# ledarray.net
KiCad netlist of a schematic drawn in EAGLE
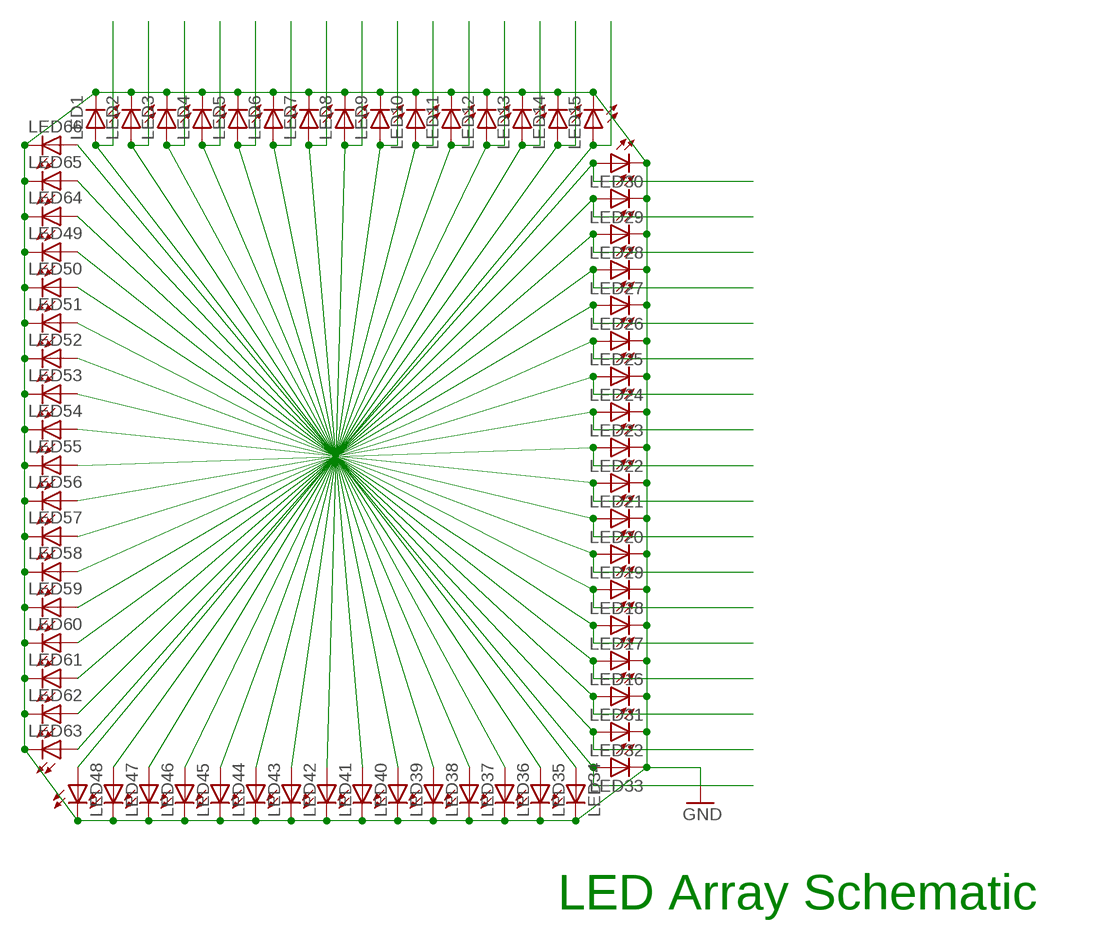
[diagram p0: schematic, sheet 1]

(export (version "E")
  (design (tool "Eeschema 10.0.6"))
  (components
    (comp (ref "LED1")
      (value "LED3MM")
      (footprint "eagle-import:LED3MM")
      (libsource (lib "eagle-import") (part "LED3MM"))
    )
    (comp (ref "LED2")
      (value "LED3MM")
      (footprint "eagle-import:LED3MM")
      (libsource (lib "eagle-import") (part "LED3MM"))
    )
    (comp (ref "LED3")
      (value "LED3MM")
      (footprint "eagle-import:LED3MM")
      (libsource (lib "eagle-import") (part "LED3MM"))
    )
    (comp (ref "LED4")
      (value "LED3MM")
      (footprint "eagle-import:LED3MM")
      (libsource (lib "eagle-import") (part "LED3MM"))
    )
    (comp (ref "LED5")
      (value "LED3MM")
      (footprint "eagle-import:LED3MM")
      (libsource (lib "eagle-import") (part "LED3MM"))
    )
    (comp (ref "LED6")
      (value "LED3MM")
      (footprint "eagle-import:LED3MM")
      (libsource (lib "eagle-import") (part "LED3MM"))
    )
    (comp (ref "LED7")
      (value "LED3MM")
      (footprint "eagle-import:LED3MM")
      (libsource (lib "eagle-import") (part "LED3MM"))
    )
    (comp (ref "LED8")
      (value "LED3MM")
      (footprint "eagle-import:LED3MM")
      (libsource (lib "eagle-import") (part "LED3MM"))
    )
    (comp (ref "LED9")
      (value "LED3MM")
      (footprint "eagle-import:LED3MM")
      (libsource (lib "eagle-import") (part "LED3MM"))
    )
    (comp (ref "LED10")
      (value "LED3MM")
      (footprint "eagle-import:LED3MM")
      (libsource (lib "eagle-import") (part "LED3MM"))
    )
    (comp (ref "LED11")
      (value "LED3MM")
      (footprint "eagle-import:LED3MM")
      (libsource (lib "eagle-import") (part "LED3MM"))
    )
    (comp (ref "LED12")
      (value "LED3MM")
      (footprint "eagle-import:LED3MM")
      (libsource (lib "eagle-import") (part "LED3MM"))
    )
    (comp (ref "LED13")
      (value "LED3MM")
      (footprint "eagle-import:LED3MM")
      (libsource (lib "eagle-import") (part "LED3MM"))
    )
    (comp (ref "LED14")
      (value "LED3MM")
      (footprint "eagle-import:LED3MM")
      (libsource (lib "eagle-import") (part "LED3MM"))
    )
    (comp (ref "LED15")
      (value "LED3MM")
      (footprint "eagle-import:LED3MM")
      (libsource (lib "eagle-import") (part "LED3MM"))
    )
    (comp (ref "LED16")
      (value "LED3MM")
      (footprint "eagle-import:LED3MM")
      (libsource (lib "eagle-import") (part "LED3MM"))
    )
    (comp (ref "LED17")
      (value "LED3MM")
      (footprint "eagle-import:LED3MM")
      (libsource (lib "eagle-import") (part "LED3MM"))
    )
    (comp (ref "LED18")
      (value "LED3MM")
      (footprint "eagle-import:LED3MM")
      (libsource (lib "eagle-import") (part "LED3MM"))
    )
    (comp (ref "LED19")
      (value "LED3MM")
      (footprint "eagle-import:LED3MM")
      (libsource (lib "eagle-import") (part "LED3MM"))
    )
    (comp (ref "LED20")
      (value "LED3MM")
      (footprint "eagle-import:LED3MM")
      (libsource (lib "eagle-import") (part "LED3MM"))
    )
    (comp (ref "LED21")
      (value "LED3MM")
      (footprint "eagle-import:LED3MM")
      (libsource (lib "eagle-import") (part "LED3MM"))
    )
    (comp (ref "LED22")
      (value "LED3MM")
      (footprint "eagle-import:LED3MM")
      (libsource (lib "eagle-import") (part "LED3MM"))
    )
    (comp (ref "LED23")
      (value "LED3MM")
      (footprint "eagle-import:LED3MM")
      (libsource (lib "eagle-import") (part "LED3MM"))
    )
    (comp (ref "LED24")
      (value "LED3MM")
      (footprint "eagle-import:LED3MM")
      (libsource (lib "eagle-import") (part "LED3MM"))
    )
    (comp (ref "LED25")
      (value "LED3MM")
      (footprint "eagle-import:LED3MM")
      (libsource (lib "eagle-import") (part "LED3MM"))
    )
    (comp (ref "LED26")
      (value "LED3MM")
      (footprint "eagle-import:LED3MM")
      (libsource (lib "eagle-import") (part "LED3MM"))
    )
    (comp (ref "LED27")
      (value "LED3MM")
      (footprint "eagle-import:LED3MM")
      (libsource (lib "eagle-import") (part "LED3MM"))
    )
    (comp (ref "LED28")
      (value "LED3MM")
      (footprint "eagle-import:LED3MM")
      (libsource (lib "eagle-import") (part "LED3MM"))
    )
    (comp (ref "LED29")
      (value "LED3MM")
      (footprint "eagle-import:LED3MM")
      (libsource (lib "eagle-import") (part "LED3MM"))
    )
    (comp (ref "LED30")
      (value "LED3MM")
      (footprint "eagle-import:LED3MM")
      (libsource (lib "eagle-import") (part "LED3MM"))
    )
    (comp (ref "LED31")
      (value "LED3MM")
      (footprint "eagle-import:LED3MM")
      (libsource (lib "eagle-import") (part "LED3MM"))
    )
    (comp (ref "LED32")
      (value "LED3MM")
      (footprint "eagle-import:LED3MM")
      (libsource (lib "eagle-import") (part "LED3MM"))
    )
    (comp (ref "LED33")
      (value "LED3MM")
      (footprint "eagle-import:LED3MM")
      (libsource (lib "eagle-import") (part "LED3MM"))
    )
    (comp (ref "LED34")
      (value "LED3MM")
      (footprint "eagle-import:LED3MM")
      (libsource (lib "eagle-import") (part "LED3MM"))
    )
    (comp (ref "LED35")
      (value "LED3MM")
      (footprint "eagle-import:LED3MM")
      (libsource (lib "eagle-import") (part "LED3MM"))
    )
    (comp (ref "LED36")
      (value "LED3MM")
      (footprint "eagle-import:LED3MM")
      (libsource (lib "eagle-import") (part "LED3MM"))
    )
    (comp (ref "LED37")
      (value "LED3MM")
      (footprint "eagle-import:LED3MM")
      (libsource (lib "eagle-import") (part "LED3MM"))
    )
    (comp (ref "LED38")
      (value "LED3MM")
      (footprint "eagle-import:LED3MM")
      (libsource (lib "eagle-import") (part "LED3MM"))
    )
    (comp (ref "LED39")
      (value "LED3MM")
      (footprint "eagle-import:LED3MM")
      (libsource (lib "eagle-import") (part "LED3MM"))
    )
    (comp (ref "LED40")
      (value "LED3MM")
      (footprint "eagle-import:LED3MM")
      (libsource (lib "eagle-import") (part "LED3MM"))
    )
    (comp (ref "LED41")
      (value "LED3MM")
      (footprint "eagle-import:LED3MM")
      (libsource (lib "eagle-import") (part "LED3MM"))
    )
    (comp (ref "LED42")
      (value "LED3MM")
      (footprint "eagle-import:LED3MM")
      (libsource (lib "eagle-import") (part "LED3MM"))
    )
    (comp (ref "LED43")
      (value "LED3MM")
      (footprint "eagle-import:LED3MM")
      (libsource (lib "eagle-import") (part "LED3MM"))
    )
    (comp (ref "LED44")
      (value "LED3MM")
      (footprint "eagle-import:LED3MM")
      (libsource (lib "eagle-import") (part "LED3MM"))
    )
    (comp (ref "LED45")
      (value "LED3MM")
      (footprint "eagle-import:LED3MM")
      (libsource (lib "eagle-import") (part "LED3MM"))
    )
    (comp (ref "LED46")
      (value "LED3MM")
      (footprint "eagle-import:LED3MM")
      (libsource (lib "eagle-import") (part "LED3MM"))
    )
    (comp (ref "LED47")
      (value "LED3MM")
      (footprint "eagle-import:LED3MM")
      (libsource (lib "eagle-import") (part "LED3MM"))
    )
    (comp (ref "LED48")
      (value "LED3MM")
      (footprint "eagle-import:LED3MM")
      (libsource (lib "eagle-import") (part "LED3MM"))
    )
    (comp (ref "LED49")
      (value "LED3MM")
      (footprint "eagle-import:LED3MM")
      (libsource (lib "eagle-import") (part "LED3MM"))
    )
    (comp (ref "LED50")
      (value "LED3MM")
      (footprint "eagle-import:LED3MM")
      (libsource (lib "eagle-import") (part "LED3MM"))
    )
    (comp (ref "LED51")
      (value "LED3MM")
      (footprint "eagle-import:LED3MM")
      (libsource (lib "eagle-import") (part "LED3MM"))
    )
    (comp (ref "LED52")
      (value "LED3MM")
      (footprint "eagle-import:LED3MM")
      (libsource (lib "eagle-import") (part "LED3MM"))
    )
    (comp (ref "LED53")
      (value "LED3MM")
      (footprint "eagle-import:LED3MM")
      (libsource (lib "eagle-import") (part "LED3MM"))
    )
    (comp (ref "LED54")
      (value "LED3MM")
      (footprint "eagle-import:LED3MM")
      (libsource (lib "eagle-import") (part "LED3MM"))
    )
    (comp (ref "LED55")
      (value "LED3MM")
      (footprint "eagle-import:LED3MM")
      (libsource (lib "eagle-import") (part "LED3MM"))
    )
    (comp (ref "LED56")
      (value "LED3MM")
      (footprint "eagle-import:LED3MM")
      (libsource (lib "eagle-import") (part "LED3MM"))
    )
    (comp (ref "LED57")
      (value "LED3MM")
      (footprint "eagle-import:LED3MM")
      (libsource (lib "eagle-import") (part "LED3MM"))
    )
    (comp (ref "LED58")
      (value "LED3MM")
      (footprint "eagle-import:LED3MM")
      (libsource (lib "eagle-import") (part "LED3MM"))
    )
    (comp (ref "LED59")
      (value "LED3MM")
      (footprint "eagle-import:LED3MM")
      (libsource (lib "eagle-import") (part "LED3MM"))
    )
    (comp (ref "LED60")
      (value "LED3MM")
      (footprint "eagle-import:LED3MM")
      (libsource (lib "eagle-import") (part "LED3MM"))
    )
    (comp (ref "LED61")
      (value "LED3MM")
      (footprint "eagle-import:LED3MM")
      (libsource (lib "eagle-import") (part "LED3MM"))
    )
    (comp (ref "LED62")
      (value "LED3MM")
      (footprint "eagle-import:LED3MM")
      (libsource (lib "eagle-import") (part "LED3MM"))
    )
    (comp (ref "LED63")
      (value "LED3MM")
      (footprint "eagle-import:LED3MM")
      (libsource (lib "eagle-import") (part "LED3MM"))
    )
    (comp (ref "LED64")
      (value "LED3MM")
      (footprint "eagle-import:LED3MM")
      (libsource (lib "eagle-import") (part "LED3MM"))
    )
    (comp (ref "LED65")
      (value "LED3MM")
      (footprint "eagle-import:LED3MM")
      (libsource (lib "eagle-import") (part "LED3MM"))
    )
    (comp (ref "LED66")
      (value "LED3MM")
      (footprint "eagle-import:LED3MM")
      (libsource (lib "eagle-import") (part "LED3MM"))
    )
  )
  (nets
    (net (code "1") (name "GND") (class "Default")
      (node (ref "LED1") (pin "K") (pinfunction "C_K") (pintype "passive"))
      (node (ref "LED10") (pin "K") (pinfunction "C_K") (pintype "passive"))
      (node (ref "LED11") (pin "K") (pinfunction "C_K") (pintype "passive"))
      (node (ref "LED12") (pin "K") (pinfunction "C_K") (pintype "passive"))
      (node (ref "LED13") (pin "K") (pinfunction "C_K") (pintype "passive"))
      (node (ref "LED14") (pin "K") (pinfunction "C_K") (pintype "passive"))
      (node (ref "LED15") (pin "K") (pinfunction "C_K") (pintype "passive"))
      (node (ref "LED16") (pin "K") (pinfunction "C_K") (pintype "passive"))
      (node (ref "LED17") (pin "K") (pinfunction "C_K") (pintype "passive"))
      (node (ref "LED18") (pin "K") (pinfunction "C_K") (pintype "passive"))
      (node (ref "LED19") (pin "K") (pinfunction "C_K") (pintype "passive"))
      (node (ref "LED2") (pin "K") (pinfunction "C_K") (pintype "passive"))
      (node (ref "LED20") (pin "K") (pinfunction "C_K") (pintype "passive"))
      (node (ref "LED21") (pin "K") (pinfunction "C_K") (pintype "passive"))
      (node (ref "LED22") (pin "K") (pinfunction "C_K") (pintype "passive"))
      (node (ref "LED23") (pin "K") (pinfunction "C_K") (pintype "passive"))
      (node (ref "LED24") (pin "K") (pinfunction "C_K") (pintype "passive"))
      (node (ref "LED25") (pin "K") (pinfunction "C_K") (pintype "passive"))
      (node (ref "LED26") (pin "K") (pinfunction "C_K") (pintype "passive"))
      (node (ref "LED27") (pin "K") (pinfunction "C_K") (pintype "passive"))
      (node (ref "LED28") (pin "K") (pinfunction "C_K") (pintype "passive"))
      (node (ref "LED29") (pin "K") (pinfunction "C_K") (pintype "passive"))
      (node (ref "LED3") (pin "K") (pinfunction "C_K") (pintype "passive"))
      (node (ref "LED30") (pin "K") (pinfunction "C_K") (pintype "passive"))
      (node (ref "LED31") (pin "K") (pinfunction "C_K") (pintype "passive"))
      (node (ref "LED32") (pin "K") (pinfunction "C_K") (pintype "passive"))
      (node (ref "LED33") (pin "K") (pinfunction "C_K") (pintype "passive"))
      (node (ref "LED34") (pin "K") (pinfunction "C_K") (pintype "passive"))
      (node (ref "LED35") (pin "K") (pinfunction "C_K") (pintype "passive"))
      (node (ref "LED36") (pin "K") (pinfunction "C_K") (pintype "passive"))
      (node (ref "LED37") (pin "K") (pinfunction "C_K") (pintype "passive"))
      (node (ref "LED38") (pin "K") (pinfunction "C_K") (pintype "passive"))
      (node (ref "LED39") (pin "K") (pinfunction "C_K") (pintype "passive"))
      (node (ref "LED4") (pin "K") (pinfunction "C_K") (pintype "passive"))
      (node (ref "LED40") (pin "K") (pinfunction "C_K") (pintype "passive"))
      (node (ref "LED41") (pin "K") (pinfunction "C_K") (pintype "passive"))
      (node (ref "LED42") (pin "K") (pinfunction "C_K") (pintype "passive"))
      (node (ref "LED43") (pin "K") (pinfunction "C_K") (pintype "passive"))
      (node (ref "LED44") (pin "K") (pinfunction "C_K") (pintype "passive"))
      (node (ref "LED45") (pin "K") (pinfunction "C_K") (pintype "passive"))
      (node (ref "LED46") (pin "K") (pinfunction "C_K") (pintype "passive"))
      (node (ref "LED47") (pin "K") (pinfunction "C_K") (pintype "passive"))
      (node (ref "LED48") (pin "K") (pinfunction "C_K") (pintype "passive"))
      (node (ref "LED49") (pin "K") (pinfunction "C_K") (pintype "passive"))
      (node (ref "LED5") (pin "K") (pinfunction "C_K") (pintype "passive"))
      (node (ref "LED50") (pin "K") (pinfunction "C_K") (pintype "passive"))
      (node (ref "LED51") (pin "K") (pinfunction "C_K") (pintype "passive"))
      (node (ref "LED52") (pin "K") (pinfunction "C_K") (pintype "passive"))
      (node (ref "LED53") (pin "K") (pinfunction "C_K") (pintype "passive"))
      (node (ref "LED54") (pin "K") (pinfunction "C_K") (pintype "passive"))
      (node (ref "LED55") (pin "K") (pinfunction "C_K") (pintype "passive"))
      (node (ref "LED56") (pin "K") (pinfunction "C_K") (pintype "passive"))
      (node (ref "LED57") (pin "K") (pinfunction "C_K") (pintype "passive"))
      (node (ref "LED58") (pin "K") (pinfunction "C_K") (pintype "passive"))
      (node (ref "LED59") (pin "K") (pinfunction "C_K") (pintype "passive"))
      (node (ref "LED6") (pin "K") (pinfunction "C_K") (pintype "passive"))
      (node (ref "LED60") (pin "K") (pinfunction "C_K") (pintype "passive"))
      (node (ref "LED61") (pin "K") (pinfunction "C_K") (pintype "passive"))
      (node (ref "LED62") (pin "K") (pinfunction "C_K") (pintype "passive"))
      (node (ref "LED63") (pin "K") (pinfunction "C_K") (pintype "passive"))
      (node (ref "LED64") (pin "K") (pinfunction "C_K") (pintype "passive"))
      (node (ref "LED65") (pin "K") (pinfunction "C_K") (pintype "passive"))
      (node (ref "LED66") (pin "K") (pinfunction "C_K") (pintype "passive"))
      (node (ref "LED7") (pin "K") (pinfunction "C_K") (pintype "passive"))
      (node (ref "LED8") (pin "K") (pinfunction "C_K") (pintype "passive"))
      (node (ref "LED9") (pin "K") (pinfunction "C_K") (pintype "passive"))
    )
    (net (code "2") (name "Net-(LED1-PadA)") (class "Default")
      (node (ref "LED1") (pin "A") (pinfunction "A_A") (pintype "passive"))
      (node (ref "LED34") (pin "A") (pinfunction "A_A") (pintype "passive"))
    )
    (net (code "3") (name "Net-(LED2-PadA)") (class "Default")
      (node (ref "LED2") (pin "A") (pinfunction "A_A") (pintype "passive"))
      (node (ref "LED35") (pin "A") (pinfunction "A_A") (pintype "passive"))
    )
    (net (code "4") (name "Net-(LED3-PadA)") (class "Default")
      (node (ref "LED3") (pin "A") (pinfunction "A_A") (pintype "passive"))
      (node (ref "LED36") (pin "A") (pinfunction "A_A") (pintype "passive"))
    )
    (net (code "5") (name "Net-(LED10-PadA)") (class "Default")
      (node (ref "LED10") (pin "A") (pinfunction "A_A") (pintype "passive"))
      (node (ref "LED43") (pin "A") (pinfunction "A_A") (pintype "passive"))
    )
    (net (code "6") (name "Net-(LED11-PadA)") (class "Default")
      (node (ref "LED11") (pin "A") (pinfunction "A_A") (pintype "passive"))
      (node (ref "LED44") (pin "A") (pinfunction "A_A") (pintype "passive"))
    )
    (net (code "7") (name "Net-(LED12-PadA)") (class "Default")
      (node (ref "LED12") (pin "A") (pinfunction "A_A") (pintype "passive"))
      (node (ref "LED45") (pin "A") (pinfunction "A_A") (pintype "passive"))
    )
    (net (code "8") (name "Net-(LED13-PadA)") (class "Default")
      (node (ref "LED13") (pin "A") (pinfunction "A_A") (pintype "passive"))
      (node (ref "LED46") (pin "A") (pinfunction "A_A") (pintype "passive"))
    )
    (net (code "9") (name "Net-(LED14-PadA)") (class "Default")
      (node (ref "LED14") (pin "A") (pinfunction "A_A") (pintype "passive"))
      (node (ref "LED47") (pin "A") (pinfunction "A_A") (pintype "passive"))
    )
    (net (code "10") (name "Net-(LED15-PadA)") (class "Default")
      (node (ref "LED15") (pin "A") (pinfunction "A_A") (pintype "passive"))
      (node (ref "LED48") (pin "A") (pinfunction "A_A") (pintype "passive"))
    )
    (net (code "11") (name "Net-(LED16-PadA)") (class "Default")
      (node (ref "LED16") (pin "A") (pinfunction "A_A") (pintype "passive"))
      (node (ref "LED49") (pin "A") (pinfunction "A_A") (pintype "passive"))
    )
    (net (code "12") (name "Net-(LED17-PadA)") (class "Default")
      (node (ref "LED17") (pin "A") (pinfunction "A_A") (pintype "passive"))
      (node (ref "LED50") (pin "A") (pinfunction "A_A") (pintype "passive"))
    )
    (net (code "13") (name "Net-(LED18-PadA)") (class "Default")
      (node (ref "LED18") (pin "A") (pinfunction "A_A") (pintype "passive"))
      (node (ref "LED51") (pin "A") (pinfunction "A_A") (pintype "passive"))
    )
    (net (code "14") (name "Net-(LED19-PadA)") (class "Default")
      (node (ref "LED19") (pin "A") (pinfunction "A_A") (pintype "passive"))
      (node (ref "LED52") (pin "A") (pinfunction "A_A") (pintype "passive"))
    )
    (net (code "15") (name "Net-(LED20-PadA)") (class "Default")
      (node (ref "LED20") (pin "A") (pinfunction "A_A") (pintype "passive"))
      (node (ref "LED53") (pin "A") (pinfunction "A_A") (pintype "passive"))
    )
    (net (code "16") (name "Net-(LED21-PadA)") (class "Default")
      (node (ref "LED21") (pin "A") (pinfunction "A_A") (pintype "passive"))
      (node (ref "LED54") (pin "A") (pinfunction "A_A") (pintype "passive"))
    )
    (net (code "17") (name "Net-(LED22-PadA)") (class "Default")
      (node (ref "LED22") (pin "A") (pinfunction "A_A") (pintype "passive"))
      (node (ref "LED55") (pin "A") (pinfunction "A_A") (pintype "passive"))
    )
    (net (code "18") (name "Net-(LED23-PadA)") (class "Default")
      (node (ref "LED23") (pin "A") (pinfunction "A_A") (pintype "passive"))
      (node (ref "LED56") (pin "A") (pinfunction "A_A") (pintype "passive"))
    )
    (net (code "19") (name "Net-(LED24-PadA)") (class "Default")
      (node (ref "LED24") (pin "A") (pinfunction "A_A") (pintype "passive"))
      (node (ref "LED57") (pin "A") (pinfunction "A_A") (pintype "passive"))
    )
    (net (code "20") (name "Net-(LED25-PadA)") (class "Default")
      (node (ref "LED25") (pin "A") (pinfunction "A_A") (pintype "passive"))
      (node (ref "LED58") (pin "A") (pinfunction "A_A") (pintype "passive"))
    )
    (net (code "21") (name "Net-(LED26-PadA)") (class "Default")
      (node (ref "LED26") (pin "A") (pinfunction "A_A") (pintype "passive"))
      (node (ref "LED59") (pin "A") (pinfunction "A_A") (pintype "passive"))
    )
    (net (code "22") (name "Net-(LED27-PadA)") (class "Default")
      (node (ref "LED27") (pin "A") (pinfunction "A_A") (pintype "passive"))
      (node (ref "LED60") (pin "A") (pinfunction "A_A") (pintype "passive"))
    )
    (net (code "23") (name "Net-(LED28-PadA)") (class "Default")
      (node (ref "LED28") (pin "A") (pinfunction "A_A") (pintype "passive"))
      (node (ref "LED61") (pin "A") (pinfunction "A_A") (pintype "passive"))
    )
    (net (code "24") (name "Net-(LED29-PadA)") (class "Default")
      (node (ref "LED29") (pin "A") (pinfunction "A_A") (pintype "passive"))
      (node (ref "LED62") (pin "A") (pinfunction "A_A") (pintype "passive"))
    )
    (net (code "25") (name "Net-(LED30-PadA)") (class "Default")
      (node (ref "LED30") (pin "A") (pinfunction "A_A") (pintype "passive"))
      (node (ref "LED63") (pin "A") (pinfunction "A_A") (pintype "passive"))
    )
    (net (code "26") (name "Net-(LED31-PadA)") (class "Default")
      (node (ref "LED31") (pin "A") (pinfunction "A_A") (pintype "passive"))
      (node (ref "LED64") (pin "A") (pinfunction "A_A") (pintype "passive"))
    )
    (net (code "27") (name "Net-(LED32-PadA)") (class "Default")
      (node (ref "LED32") (pin "A") (pinfunction "A_A") (pintype "passive"))
      (node (ref "LED65") (pin "A") (pinfunction "A_A") (pintype "passive"))
    )
    (net (code "28") (name "Net-(LED33-PadA)") (class "Default")
      (node (ref "LED33") (pin "A") (pinfunction "A_A") (pintype "passive"))
      (node (ref "LED66") (pin "A") (pinfunction "A_A") (pintype "passive"))
    )
    (net (code "29") (name "Net-(LED37-PadA)") (class "Default")
      (node (ref "LED37") (pin "A") (pinfunction "A_A") (pintype "passive"))
      (node (ref "LED4") (pin "A") (pinfunction "A_A") (pintype "passive"))
    )
    (net (code "30") (name "Net-(LED38-PadA)") (class "Default")
      (node (ref "LED38") (pin "A") (pinfunction "A_A") (pintype "passive"))
      (node (ref "LED5") (pin "A") (pinfunction "A_A") (pintype "passive"))
    )
    (net (code "31") (name "Net-(LED39-PadA)") (class "Default")
      (node (ref "LED39") (pin "A") (pinfunction "A_A") (pintype "passive"))
      (node (ref "LED6") (pin "A") (pinfunction "A_A") (pintype "passive"))
    )
    (net (code "32") (name "Net-(LED40-PadA)") (class "Default")
      (node (ref "LED40") (pin "A") (pinfunction "A_A") (pintype "passive"))
      (node (ref "LED7") (pin "A") (pinfunction "A_A") (pintype "passive"))
    )
    (net (code "33") (name "Net-(LED41-PadA)") (class "Default")
      (node (ref "LED41") (pin "A") (pinfunction "A_A") (pintype "passive"))
      (node (ref "LED8") (pin "A") (pinfunction "A_A") (pintype "passive"))
    )
    (net (code "34") (name "Net-(LED42-PadA)") (class "Default")
      (node (ref "LED42") (pin "A") (pinfunction "A_A") (pintype "passive"))
      (node (ref "LED9") (pin "A") (pinfunction "A_A") (pintype "passive"))
    )
  )
)
